# Sheet1.net
KiCad netlist of a schematic drawn in Altium Designer
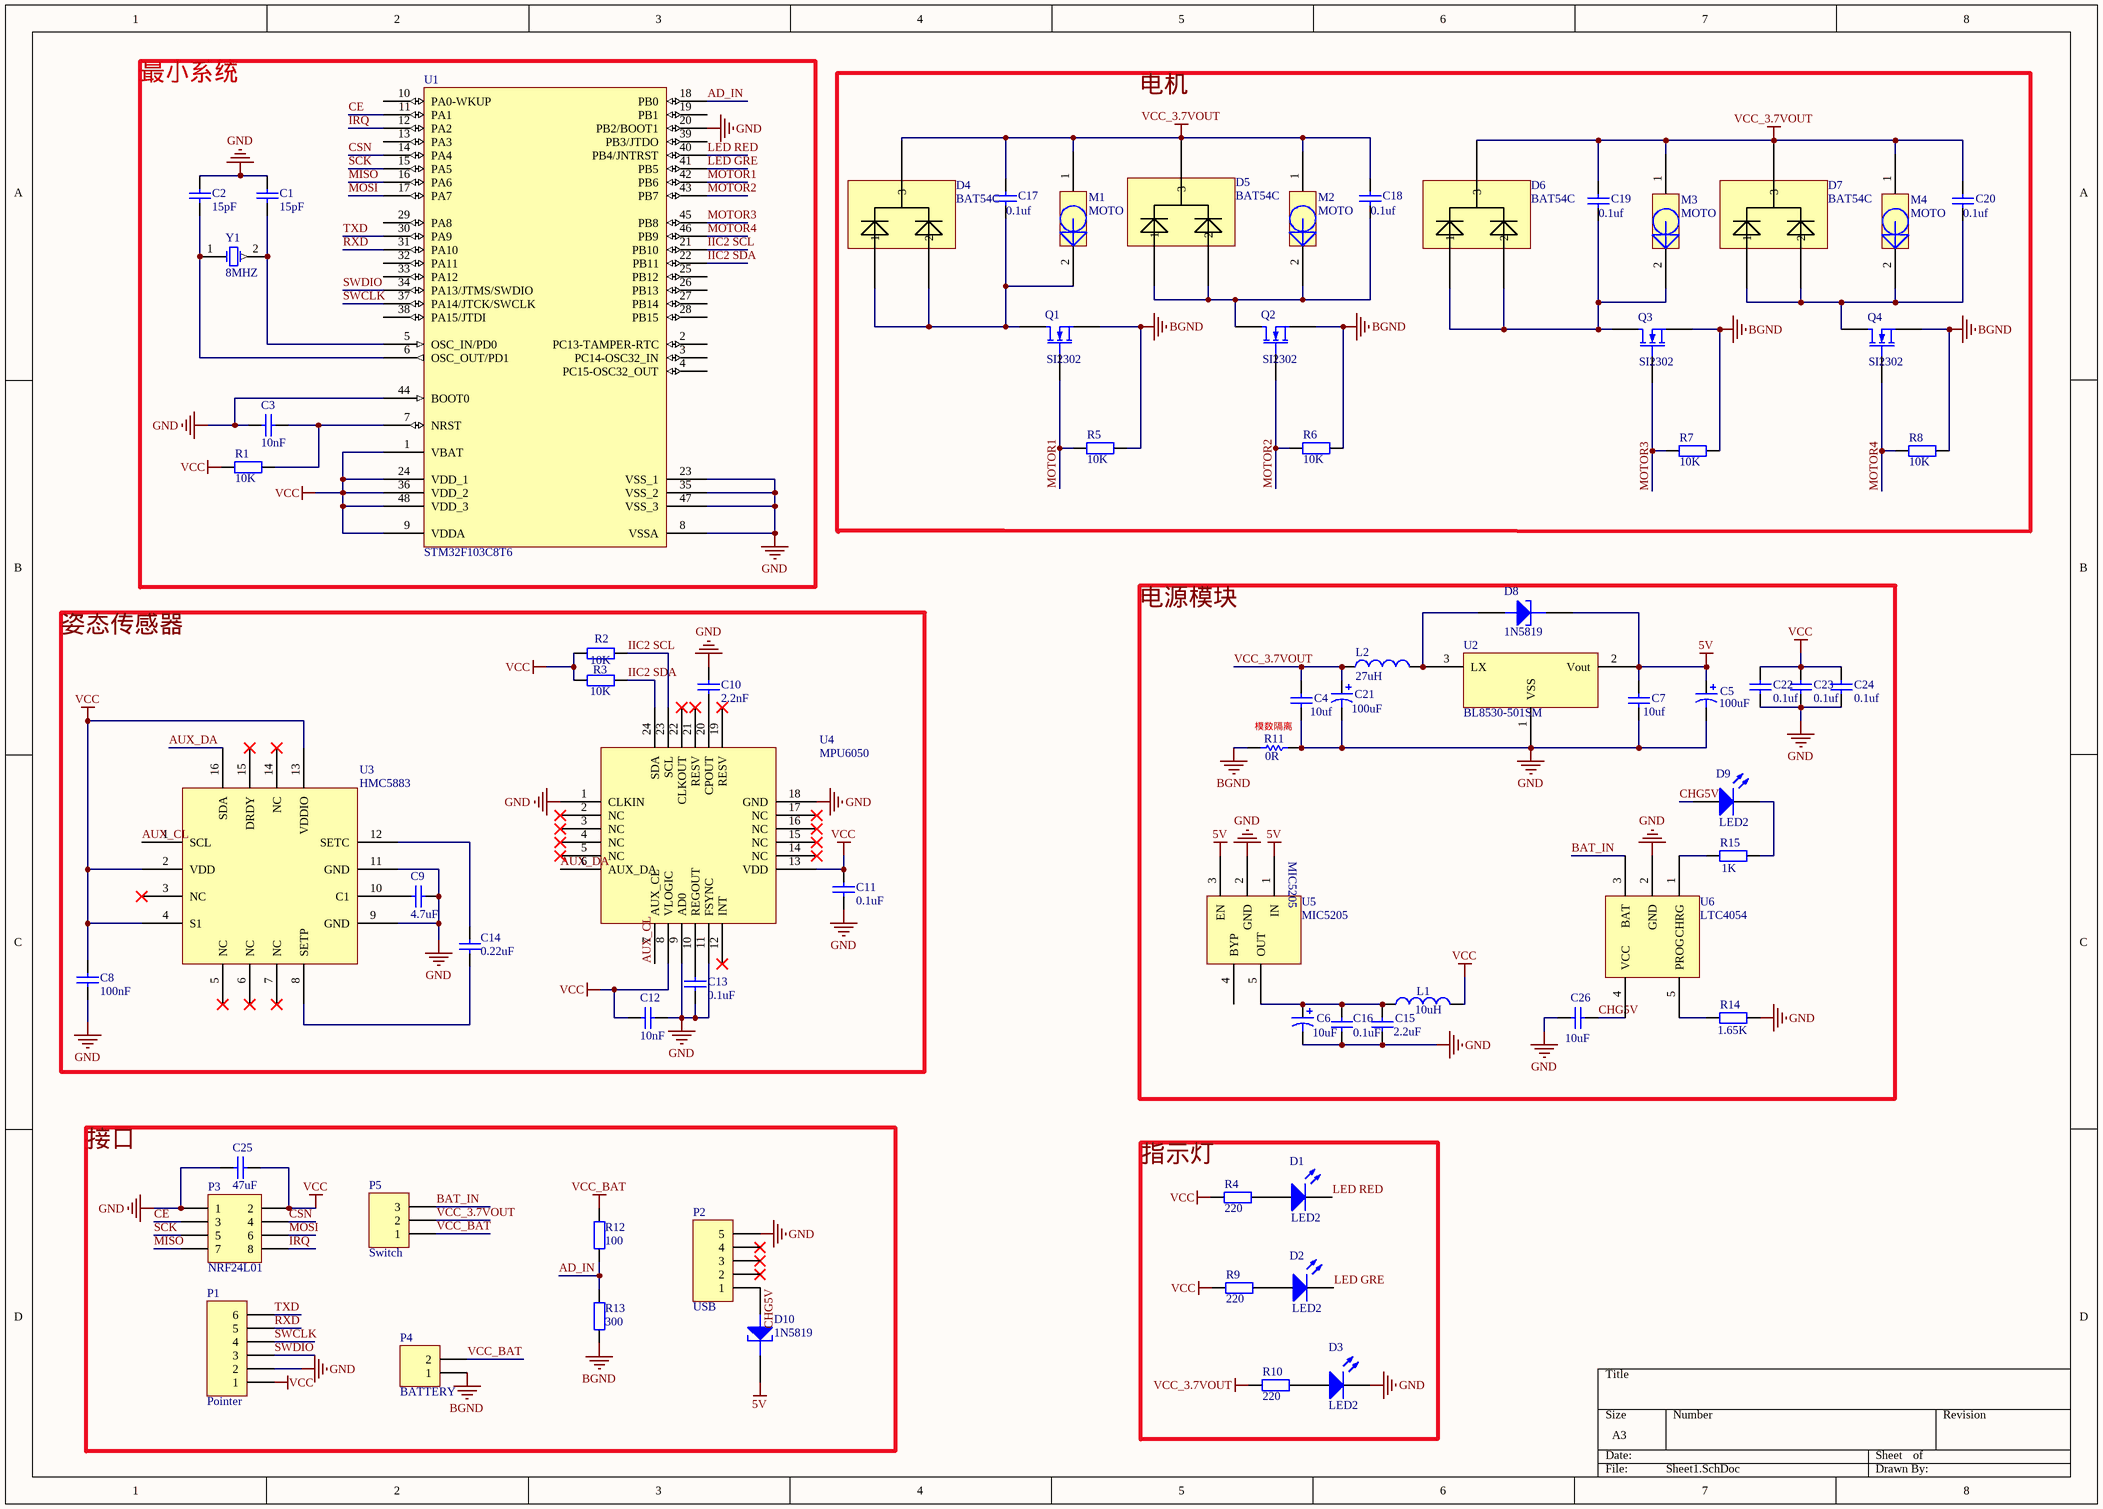
[diagram p0: Sheet1.SchDoc]

(export (version "E")
  (design (tool "Eeschema 10.0.6"))
  (components
    (comp (ref "C1")
      (value "15pF")
      (footprint "0603-N-CAP")
      (description "Capacitor (Semiconductor SIM Model)")
      (fields (field (name "Comment") "Cap Semi") (field (name "PUBLISHER") "Altium Limited"))
      (libsource (lib "Miscellaneous Devices") (part "Cap Semi"))
    )
    (comp (ref "C2")
      (value "15pF")
      (footprint "0603-N-CAP")
      (description "Capacitor (Semiconductor SIM Model)")
      (fields (field (name "Comment") "Cap Semi") (field (name "PUBLISHER") "Altium Limited"))
      (libsource (lib "Miscellaneous Devices") (part "Cap Semi"))
    )
    (comp (ref "C3")
      (value "10nF")
      (footprint "0603-N-CAP")
      (description "Capacitor (Semiconductor SIM Model)")
      (fields (field (name "Comment") "Cap Semi") (field (name "PUBLISHER") "Altium Limited"))
      (libsource (lib "Miscellaneous Devices") (part "Cap Semi"))
    )
    (comp (ref "C4")
      (value "10uf")
      (footprint "0603-N-CAP")
      (description "Capacitor")
      (fields (field (name "Comment") "Cap") (field (name "PUBLISHER") "Altium Limited"))
      (libsource (lib "Miscellaneous Devices") (part "Cap"))
    )
    (comp (ref "C5")
      (value "100uF")
      (footprint "1210")
      (description "Polarized Capacitor (Surface Mount)")
      (fields (field (name "Comment") "Cap Pol3") (field (name "PUBLISHER") "Altium Limited"))
      (libsource (lib "Miscellaneous Devices") (part "Cap Pol3"))
    )
    (comp (ref "C6")
      (value "10uF")
      (footprint "3216")
      (description "Polarized Capacitor (Surface Mount)")
      (fields (field (name "Comment") "Cap Pol3") (field (name "PUBLISHER") "Altium Limited"))
      (libsource (lib "Miscellaneous Devices") (part "Cap Pol3"))
    )
    (comp (ref "C7")
      (value "10uf")
      (footprint "0603-N-CAP")
      (description "Capacitor")
      (fields (field (name "Comment") "Cap") (field (name "PUBLISHER") "Altium Limited"))
      (libsource (lib "Miscellaneous Devices") (part "Cap"))
    )
    (comp (ref "C8")
      (value "100nF")
      (footprint "0603-N-CAP")
      (description "Capacitor (Semiconductor SIM Model)")
      (fields (field (name "Comment") "Cap Semi") (field (name "PUBLISHER") "Altium Limited"))
      (libsource (lib "Miscellaneous Devices") (part "Cap Semi"))
    )
    (comp (ref "C9")
      (value "4.7uF")
      (footprint "0603-N-CAP")
      (description "Capacitor (Semiconductor SIM Model)")
      (fields (field (name "Comment") "Cap Semi") (field (name "PUBLISHER") "Altium Limited"))
      (libsource (lib "Miscellaneous Devices") (part "Cap Semi"))
    )
    (comp (ref "C10")
      (value "2.2nF")
      (footprint "0603-N-CAP")
      (description "Capacitor (Semiconductor SIM Model)")
      (fields (field (name "Comment") "Cap Semi") (field (name "PUBLISHER") "Altium Limited"))
      (libsource (lib "Miscellaneous Devices") (part "Cap Semi"))
    )
    (comp (ref "C11")
      (value "0.1uF")
      (footprint "0603-N-CAP")
      (description "Capacitor (Semiconductor SIM Model)")
      (fields (field (name "Comment") "Cap Semi") (field (name "PUBLISHER") "Altium Limited"))
      (libsource (lib "Miscellaneous Devices") (part "Cap Semi"))
    )
    (comp (ref "C12")
      (value "10nF")
      (footprint "0603-N-CAP")
      (description "Capacitor (Semiconductor SIM Model)")
      (fields (field (name "Comment") "Cap Semi") (field (name "PUBLISHER") "Altium Limited"))
      (libsource (lib "Miscellaneous Devices") (part "Cap Semi"))
    )
    (comp (ref "C13")
      (value "0.1uF")
      (footprint "0603-N-CAP")
      (description "Capacitor (Semiconductor SIM Model)")
      (fields (field (name "Comment") "Cap Semi") (field (name "PUBLISHER") "Altium Limited"))
      (libsource (lib "Miscellaneous Devices") (part "Cap Semi"))
    )
    (comp (ref "C14")
      (value "0.22uF")
      (footprint "0603-N-CAP")
      (description "Capacitor (Semiconductor SIM Model)")
      (fields (field (name "Comment") "Cap Semi") (field (name "PUBLISHER") "Altium Limited"))
      (libsource (lib "Miscellaneous Devices") (part "Cap Semi"))
    )
    (comp (ref "C15")
      (value "2.2uF")
      (footprint "0603-N-CAP")
      (description "Capacitor")
      (fields (field (name "Comment") "Cap") (field (name "PUBLISHER") "Altium Limited"))
      (libsource (lib "Miscellaneous Devices") (part "Cap"))
    )
    (comp (ref "C16")
      (value "0.1uF")
      (footprint "0603-N-CAP")
      (description "Capacitor")
      (fields (field (name "Comment") "Cap") (field (name "PUBLISHER") "Altium Limited"))
      (libsource (lib "Miscellaneous Devices") (part "Cap"))
    )
    (comp (ref "C17")
      (value "0.1uf")
      (footprint "0603-N-CAP")
      (description "Capacitor")
      (fields (field (name "Comment") "Cap") (field (name "PUBLISHER") "Altium Limited"))
      (libsource (lib "Miscellaneous Devices") (part "Cap"))
    )
    (comp (ref "C18")
      (value "0.1uf")
      (footprint "0603-N-CAP")
      (description "Capacitor")
      (fields (field (name "Comment") "Cap") (field (name "PUBLISHER") "Altium Limited"))
      (libsource (lib "Miscellaneous Devices") (part "Cap"))
    )
    (comp (ref "C19")
      (value "0.1uf")
      (footprint "0603-N-CAP")
      (description "Capacitor")
      (fields (field (name "Comment") "Cap") (field (name "PUBLISHER") "Altium Limited"))
      (libsource (lib "Miscellaneous Devices") (part "Cap"))
    )
    (comp (ref "C20")
      (value "0.1uf")
      (footprint "0603-N-CAP")
      (description "Capacitor")
      (fields (field (name "Comment") "Cap") (field (name "PUBLISHER") "Altium Limited"))
      (libsource (lib "Miscellaneous Devices") (part "Cap"))
    )
    (comp (ref "C21")
      (value "100uF")
      (footprint "1210")
      (description "Polarized Capacitor (Surface Mount)")
      (fields (field (name "Comment") "Cap Pol3") (field (name "PUBLISHER") "Altium Limited"))
      (libsource (lib "Miscellaneous Devices") (part "Cap Pol3"))
    )
    (comp (ref "C22")
      (value "0.1uf")
      (footprint "0603-N-CAP")
      (description "Capacitor")
      (fields (field (name "Comment") "Cap") (field (name "PUBLISHER") "Altium Limited"))
      (libsource (lib "Miscellaneous Devices") (part "Cap"))
    )
    (comp (ref "C23")
      (value "0.1uf")
      (footprint "0603-N-CAP")
      (description "Capacitor")
      (fields (field (name "Comment") "Cap") (field (name "PUBLISHER") "Altium Limited"))
      (libsource (lib "Miscellaneous Devices") (part "Cap"))
    )
    (comp (ref "C24")
      (value "0.1uf")
      (footprint "0603-N-CAP")
      (description "Capacitor")
      (fields (field (name "Comment") "Cap") (field (name "PUBLISHER") "Altium Limited"))
      (libsource (lib "Miscellaneous Devices") (part "Cap"))
    )
    (comp (ref "C25")
      (value "47uF")
      (footprint "1206")
      (description "Capacitor (Semiconductor SIM Model)")
      (fields (field (name "Comment") "Cap Semi") (field (name "PUBLISHER") "Altium Limited"))
      (libsource (lib "Miscellaneous Devices") (part "Cap Semi"))
    )
    (comp (ref "C26")
      (value "10uF")
      (footprint "0603-N-CAP")
      (description "Capacitor")
      (fields (field (name "Comment") "Cap") (field (name "PUBLISHER") "Altium Limited"))
      (libsource (lib "Miscellaneous Devices") (part "Cap"))
    )
    (comp (ref "D1")
      (value "LED2")
      (footprint "6-0805_N")
      (description "Typical RED, GREEN, YELLOW, AMBER GaAs LED")
      (fields (field (name "PUBLISHER") "Altium Limited"))
      (libsource (lib "Miscellaneous Devices") (part "LED2"))
    )
    (comp (ref "D2")
      (value "LED2")
      (footprint "6-0805_N")
      (description "Typical RED, GREEN, YELLOW, AMBER GaAs LED")
      (fields (field (name "PUBLISHER") "Altium Limited"))
      (libsource (lib "Miscellaneous Devices") (part "LED2"))
    )
    (comp (ref "D3")
      (value "LED2")
      (footprint "6-0805_N")
      (description "Typical RED, GREEN, YELLOW, AMBER GaAs LED")
      (fields (field (name "PUBLISHER") "Altium Limited"))
      (libsource (lib "Miscellaneous Devices") (part "LED2"))
    )
    (comp (ref "D4") (value "BAT54C") (footprint "SOT-23") (libsource (lib "Mine") (part "BAT54C")))
    (comp (ref "D5") (value "BAT54C") (footprint "SOT-23") (libsource (lib "Mine") (part "BAT54C")))
    (comp (ref "D6") (value "BAT54C") (footprint "SOT-23") (libsource (lib "Mine") (part "BAT54C")))
    (comp (ref "D7") (value "BAT54C") (footprint "SOT-23") (libsource (lib "Mine") (part "BAT54C")))
    (comp (ref "D8")
      (value "1N5819")
      (footprint "1206")
      (description "Tunnel FDiode")
      (libsource (lib "二极管") (part "TUNNEL"))
    )
    (comp (ref "D9")
      (value "LED2")
      (footprint "6-0805_N")
      (description "Typical RED, GREEN, YELLOW, AMBER GaAs LED")
      (fields (field (name "PUBLISHER") "Altium Limited"))
      (libsource (lib "Miscellaneous Devices") (part "LED2"))
    )
    (comp (ref "D10")
      (value "1N5819")
      (footprint "1206")
      (description "Tunnel FDiode")
      (libsource (lib "二极管") (part "TUNNEL"))
    )
    (comp (ref "L1")
      (value "10uH")
      (footprint "0603-N-res")
      (description "Inductor")
      (fields (field (name "PUBLISHER") "Altium Limited"))
      (libsource (lib "Miscellaneous Devices") (part "Inductor"))
    )
    (comp (ref "L2")
      (value "27uH")
      (footprint "0603-N-res")
      (description "Inductor")
      (fields (field (name "PUBLISHER") "Altium Limited"))
      (libsource (lib "Miscellaneous Devices") (part "Inductor"))
    )
    (comp (ref "M1") (value "MOTO") (footprint "HDR1X2") (libsource (lib "Schlib1") (part "MOTO")))
    (comp (ref "M2") (value "MOTO") (footprint "HDR1X2") (libsource (lib "Schlib1") (part "MOTO")))
    (comp (ref "M3") (value "MOTO") (footprint "HDR1X2") (libsource (lib "Schlib1") (part "MOTO")))
    (comp (ref "M4") (value "MOTO") (footprint "HDR1X2") (libsource (lib "Schlib1") (part "MOTO")))
    (comp (ref "P1")
      (value "Pointer")
      (footprint "HDR1X6")
      (description "Header, 6-Pin")
      (fields (field (name "PUBLISHER") "Altium Limited"))
      (libsource (lib "Miscellaneous Connectors") (part "Header 6"))
    )
    (comp (ref "P2")
      (value "USB")
      (footprint "Micro Usb")
      (description "Header, 5-Pin")
      (fields (field (name "PUBLISHER") "Altium Limited"))
      (libsource (lib "Miscellaneous Connectors") (part "Header 5"))
    )
    (comp (ref "P3")
      (value "NRF24L01")
      (footprint "head 4X2")
      (description "Header, 4-Pin, Dual row, Right Angle")
      (fields (field (name "PUBLISHER") "Altium Limited"))
      (libsource (lib "Miscellaneous Connectors") (part "Header 4X2H"))
    )
    (comp (ref "P4")
      (value "BATTERY")
      (footprint "HDR1X2")
      (description "Header, 2-Pin")
      (fields (field (name "PUBLISHER") "Altium Limited"))
      (libsource (lib "Miscellaneous Connectors") (part "Header 2"))
    )
    (comp (ref "P5")
      (value "Switch")
      (footprint "HDR1X3")
      (description "Header, 3-Pin")
      (fields (field (name "PUBLISHER") "Altium Limited"))
      (libsource (lib "Miscellaneous Connectors") (part "Header 3"))
    )
    (comp (ref "Q1")
      (value "SI2302")
      (footprint "SOT-23")
      (description "N-Channel MOSFET")
      (fields (field (name "PUBLISHER") "Altium Limited"))
      (libsource (lib "Miscellaneous Devices") (part "MOSFET-N"))
    )
    (comp (ref "Q2")
      (value "SI2302")
      (footprint "SOT-23")
      (description "N-Channel MOSFET")
      (fields (field (name "PUBLISHER") "Altium Limited"))
      (libsource (lib "Miscellaneous Devices") (part "MOSFET-N"))
    )
    (comp (ref "Q3")
      (value "SI2302")
      (footprint "SOT-23")
      (description "N-Channel MOSFET")
      (fields (field (name "PUBLISHER") "Altium Limited"))
      (libsource (lib "Miscellaneous Devices") (part "MOSFET-N"))
    )
    (comp (ref "Q4")
      (value "SI2302")
      (footprint "SOT-23")
      (description "N-Channel MOSFET")
      (fields (field (name "PUBLISHER") "Altium Limited"))
      (libsource (lib "Miscellaneous Devices") (part "MOSFET-N"))
    )
    (comp (ref "R1")
      (value "10K")
      (footprint "0603-N-res")
      (description "Resistor")
      (fields (field (name "Comment") "Res2") (field (name "PUBLISHER") "Altium Limited"))
      (libsource (lib "Miscellaneous Devices") (part "Res2"))
    )
    (comp (ref "R2")
      (value "10K")
      (footprint "0603-N-res")
      (description "Resistor")
      (fields (field (name "Comment") "Res2") (field (name "PUBLISHER") "Altium Limited"))
      (libsource (lib "Miscellaneous Devices") (part "Res2"))
    )
    (comp (ref "R3")
      (value "10K")
      (footprint "0603-N-res")
      (description "Resistor")
      (fields (field (name "Comment") "Res2") (field (name "PUBLISHER") "Altium Limited"))
      (libsource (lib "Miscellaneous Devices") (part "Res2"))
    )
    (comp (ref "R4")
      (value "220")
      (footprint "0603-N-res")
      (description "Resistor")
      (fields (field (name "Comment") "Res2") (field (name "PUBLISHER") "Altium Limited"))
      (libsource (lib "Miscellaneous Devices") (part "Res2"))
    )
    (comp (ref "R5")
      (value "10K")
      (footprint "0603-N-res")
      (description "Resistor")
      (fields (field (name "Comment") "Res2") (field (name "PUBLISHER") "Altium Limited"))
      (libsource (lib "Miscellaneous Devices") (part "Res2"))
    )
    (comp (ref "R6")
      (value "10K")
      (footprint "0603-N-res")
      (description "Resistor")
      (fields (field (name "Comment") "Res2") (field (name "PUBLISHER") "Altium Limited"))
      (libsource (lib "Miscellaneous Devices") (part "Res2"))
    )
    (comp (ref "R7")
      (value "10K")
      (footprint "0603-N-res")
      (description "Resistor")
      (fields (field (name "Comment") "Res2") (field (name "PUBLISHER") "Altium Limited"))
      (libsource (lib "Miscellaneous Devices") (part "Res2"))
    )
    (comp (ref "R8")
      (value "10K")
      (footprint "0603-N-res")
      (description "Resistor")
      (fields (field (name "Comment") "Res2") (field (name "PUBLISHER") "Altium Limited"))
      (libsource (lib "Miscellaneous Devices") (part "Res2"))
    )
    (comp (ref "R9")
      (value "220")
      (footprint "0603-N-res")
      (description "Resistor")
      (fields (field (name "Comment") "Res2") (field (name "PUBLISHER") "Altium Limited"))
      (libsource (lib "Miscellaneous Devices") (part "Res2"))
    )
    (comp (ref "R10")
      (value "220")
      (footprint "0603-N-res")
      (description "Resistor")
      (fields (field (name "Comment") "Res2") (field (name "PUBLISHER") "Altium Limited"))
      (libsource (lib "Miscellaneous Devices") (part "Res2"))
    )
    (comp (ref "R11")
      (value "0R")
      (footprint "0603-N-res")
      (description "Resistor")
      (fields (field (name "Comment") "Res1") (field (name "PUBLISHER") "Altium Limited"))
      (libsource (lib "Miscellaneous Devices") (part "Res1"))
    )
    (comp (ref "R12")
      (value "100")
      (footprint "0603-N-res")
      (description "Resistor")
      (fields (field (name "Comment") "Res2") (field (name "PUBLISHER") "Altium Limited"))
      (libsource (lib "") (part "Res2_1"))
    )
    (comp (ref "R13")
      (value "300")
      (footprint "0603-N-res")
      (description "Resistor")
      (fields (field (name "Comment") "Res2") (field (name "PUBLISHER") "Altium Limited"))
      (libsource (lib "") (part "Res2_1"))
    )
    (comp (ref "R14")
      (value "1.65K")
      (footprint "0603-N-res")
      (description "Resistor")
      (fields (field (name "Comment") "Res2") (field (name "PUBLISHER") "Altium Limited"))
      (libsource (lib "") (part "Res2_2"))
    )
    (comp (ref "R15")
      (value "1K")
      (footprint "0603-N-res")
      (description "Resistor")
      (fields (field (name "Comment") "Res2") (field (name "PUBLISHER") "Altium Limited"))
      (libsource (lib "") (part "Res2_2"))
    )
    (comp (ref "U1")
      (value "STM32F103C8T6")
      (footprint "LQFP48_N")
      (description "STM32 ARM-based 32-bit MCU with 64 Kbytes Flash, 48-pin LQFP, Industrial Temperature")
      (fields (field (name "PUBLISHER") "Altium Limited"))
      (libsource (lib "ST Microcontroller 32-Bit STM32") (part "STM32F103C8T6"))
    )
    (comp (ref "U2")
      (value "BL8530-501SM")
      (footprint "SOT223")
      (libsource (lib "Schlib1") (part "ME620633"))
    )
    (comp (ref "U3") (value "HMC5883") (footprint "HMC5883L") (libsource (lib "Mine") (part "HMC5883")))
    (comp (ref "U4") (value "MPU6050") (footprint "MPU 6050") (libsource (lib "Mine") (part "MPU6050")))
    (comp (ref "U5")
      (value "MIC5205")
      (footprint "MIC5205")
      (description "5V降压到3.3V")
      (libsource (lib "Schlib1") (part "MIC5205"))
    )
    (comp (ref "U6") (value "LTC4054") (footprint "MIC5205") (libsource (lib "Mine") (part "LTC4054")))
    (comp (ref "Y1")
      (value "8MHZ")
      (footprint "XTAL1")
      (description "Crystal Oscillator")
      (fields (field (name "PUBLISHER") "Altium Limited"))
      (libsource (lib "Miscellaneous Devices") (part "XTAL"))
    )
  )
  (nets
    (net (code "1") (name "/AD_IN") (class "Default")
      (node (ref "R12") (pin "1") (pinfunction "1_1") (pintype "passive"))
      (node (ref "R13") (pin "2") (pinfunction "2_2") (pintype "passive"))
      (node (ref "U1") (pin "18") (pinfunction "PB0_18") (pintype "bidirectional"))
    )
    (net (code "2") (name "/AUX_CL") (class "Default")
      (node (ref "U3") (pin "1") (pinfunction "SCL_1") (pintype "passive"))
      (node (ref "U4") (pin "7") (pinfunction "AUX_CL_7") (pintype "passive"))
    )
    (net (code "3") (name "/AUX_DA") (class "Default")
      (node (ref "U3") (pin "16") (pinfunction "SDA_16") (pintype "passive"))
      (node (ref "U4") (pin "6") (pinfunction "AUX_DA_6") (pintype "passive"))
    )
    (net (code "4") (name "/BAT_IN") (class "Default")
      (node (ref "P5") (pin "3") (pinfunction "3_3") (pintype "passive"))
      (node (ref "U6") (pin "3") (pinfunction "BAT_3") (pintype "passive"))
    )
    (net (code "5") (name "/CE") (class "Default")
      (node (ref "P3") (pin "3") (pinfunction "3_3") (pintype "passive"))
      (node (ref "U1") (pin "11") (pinfunction "PA1_11") (pintype "bidirectional"))
    )
    (net (code "6") (name "/CHG5V") (class "Default")
      (node (ref "C26") (pin "2") (pinfunction "2_2") (pintype "passive"))
      (node (ref "D10") (pin "1") (pinfunction "A_1") (pintype "passive"))
      (node (ref "D9") (pin "1") (pinfunction "A_1") (pintype "passive"))
      (node (ref "P2") (pin "1") (pinfunction "1_1") (pintype "passive"))
      (node (ref "U6") (pin "4") (pinfunction "VCC_4") (pintype "passive"))
    )
    (net (code "7") (name "/CSN") (class "Default")
      (node (ref "P3") (pin "4") (pinfunction "4_4") (pintype "passive"))
      (node (ref "U1") (pin "14") (pinfunction "PA4_14") (pintype "bidirectional"))
    )
    (net (code "8") (name "/IIC2 SCL") (class "Default")
      (node (ref "R2") (pin "1") (pinfunction "1_1") (pintype "passive"))
      (node (ref "U1") (pin "21") (pinfunction "PB10_21") (pintype "bidirectional"))
      (node (ref "U4") (pin "23") (pinfunction "SCL_23") (pintype "passive"))
    )
    (net (code "9") (name "/IIC2 SDA") (class "Default")
      (node (ref "R3") (pin "1") (pinfunction "1_1") (pintype "passive"))
      (node (ref "U1") (pin "22") (pinfunction "PB11_22") (pintype "bidirectional"))
      (node (ref "U4") (pin "24") (pinfunction "SDA_24") (pintype "passive"))
    )
    (net (code "10") (name "/IRQ") (class "Default")
      (node (ref "P3") (pin "8") (pinfunction "8_8") (pintype "passive"))
      (node (ref "U1") (pin "12") (pinfunction "PA2_12") (pintype "bidirectional"))
    )
    (net (code "11") (name "/LED GRE") (class "Default")
      (node (ref "D2") (pin "2") (pinfunction "K_2") (pintype "passive"))
      (node (ref "U1") (pin "41") (pinfunction "PB5_41") (pintype "bidirectional"))
    )
    (net (code "12") (name "/LED RED") (class "Default")
      (node (ref "D1") (pin "2") (pinfunction "K_2") (pintype "passive"))
      (node (ref "U1") (pin "40") (pinfunction "PB4/JNTRST_40") (pintype "bidirectional"))
    )
    (net (code "13") (name "/MISO") (class "Default")
      (node (ref "P3") (pin "7") (pinfunction "7_7") (pintype "passive"))
      (node (ref "U1") (pin "16") (pinfunction "PA6_16") (pintype "bidirectional"))
    )
    (net (code "14") (name "/MOSI") (class "Default")
      (node (ref "P3") (pin "6") (pinfunction "6_6") (pintype "passive"))
      (node (ref "U1") (pin "17") (pinfunction "PA7_17") (pintype "bidirectional"))
    )
    (net (code "15") (name "/MOTOR1") (class "Default")
      (node (ref "Q1") (pin "2") (pinfunction "G_2") (pintype "passive"))
      (node (ref "R5") (pin "2") (pinfunction "2_2") (pintype "passive"))
      (node (ref "U1") (pin "42") (pinfunction "PB6_42") (pintype "bidirectional"))
    )
    (net (code "16") (name "/MOTOR2") (class "Default")
      (node (ref "Q2") (pin "2") (pinfunction "G_2") (pintype "passive"))
      (node (ref "R6") (pin "2") (pinfunction "2_2") (pintype "passive"))
      (node (ref "U1") (pin "43") (pinfunction "PB7_43") (pintype "bidirectional"))
    )
    (net (code "17") (name "/MOTOR3") (class "Default")
      (node (ref "Q3") (pin "2") (pinfunction "G_2") (pintype "passive"))
      (node (ref "R7") (pin "2") (pinfunction "2_2") (pintype "passive"))
      (node (ref "U1") (pin "45") (pinfunction "PB8_45") (pintype "bidirectional"))
    )
    (net (code "18") (name "/MOTOR4") (class "Default")
      (node (ref "Q4") (pin "2") (pinfunction "G_2") (pintype "passive"))
      (node (ref "R8") (pin "2") (pinfunction "2_2") (pintype "passive"))
      (node (ref "U1") (pin "46") (pinfunction "PB9_46") (pintype "bidirectional"))
    )
    (net (code "19") (name "/RXD") (class "Default")
      (node (ref "P1") (pin "5") (pinfunction "5_5") (pintype "passive"))
      (node (ref "U1") (pin "31") (pinfunction "PA10_31") (pintype "bidirectional"))
    )
    (net (code "20") (name "/SCK") (class "Default")
      (node (ref "P3") (pin "5") (pinfunction "5_5") (pintype "passive"))
      (node (ref "U1") (pin "15") (pinfunction "PA5_15") (pintype "bidirectional"))
    )
    (net (code "21") (name "/SWCLK") (class "Default")
      (node (ref "P1") (pin "4") (pinfunction "4_4") (pintype "passive"))
      (node (ref "U1") (pin "37") (pinfunction "PA14/JTCK/SWCLK_37") (pintype "bidirectional"))
    )
    (net (code "22") (name "/SWDIO") (class "Default")
      (node (ref "P1") (pin "3") (pinfunction "3_3") (pintype "passive"))
      (node (ref "U1") (pin "34") (pinfunction "PA13/JTMS/SWDIO_34") (pintype "bidirectional"))
    )
    (net (code "23") (name "/TXD") (class "Default")
      (node (ref "P1") (pin "6") (pinfunction "6_6") (pintype "passive"))
      (node (ref "U1") (pin "30") (pinfunction "PA9_30") (pintype "bidirectional"))
    )
    (net (code "24") (name "5V") (class "Default")
      (node (ref "C5") (pin "1") (pinfunction "1_1") (pintype "passive"))
      (node (ref "C7") (pin "2") (pinfunction "2_2") (pintype "passive"))
      (node (ref "D10") (pin "2") (pinfunction "K_2") (pintype "passive"))
      (node (ref "D8") (pin "2") (pinfunction "K_2") (pintype "passive"))
      (node (ref "U2") (pin "2") (pinfunction "Vout_2") (pintype "passive"))
      (node (ref "U5") (pin "1") (pinfunction "IN_1") (pintype "passive"))
      (node (ref "U5") (pin "3") (pinfunction "EN_3") (pintype "passive"))
    )
    (net (code "25") (name "BGND") (class "Default")
      (node (ref "P4") (pin "1") (pinfunction "1_1") (pintype "passive"))
      (node (ref "Q1") (pin "3") (pinfunction "S_3") (pintype "passive"))
      (node (ref "Q2") (pin "3") (pinfunction "S_3") (pintype "passive"))
      (node (ref "Q3") (pin "3") (pinfunction "S_3") (pintype "passive"))
      (node (ref "Q4") (pin "3") (pinfunction "S_3") (pintype "passive"))
      (node (ref "R11") (pin "1") (pinfunction "1_1") (pintype "passive"))
      (node (ref "R13") (pin "1") (pinfunction "1_1") (pintype "passive"))
      (node (ref "R5") (pin "1") (pinfunction "1_1") (pintype "passive"))
      (node (ref "R6") (pin "1") (pinfunction "1_1") (pintype "passive"))
      (node (ref "R7") (pin "1") (pinfunction "1_1") (pintype "passive"))
      (node (ref "R8") (pin "1") (pinfunction "1_1") (pintype "passive"))
    )
    (net (code "26") (name "GND") (class "Default")
      (node (ref "C1") (pin "1") (pinfunction "1_1") (pintype "passive"))
      (node (ref "C10") (pin "2") (pinfunction "2_2") (pintype "passive"))
      (node (ref "C11") (pin "1") (pinfunction "1_1") (pintype "passive"))
      (node (ref "C12") (pin "2") (pinfunction "2_2") (pintype "passive"))
      (node (ref "C13") (pin "1") (pinfunction "1_1") (pintype "passive"))
      (node (ref "C15") (pin "1") (pinfunction "1_1") (pintype "passive"))
      (node (ref "C16") (pin "1") (pinfunction "1_1") (pintype "passive"))
      (node (ref "C2") (pin "2") (pinfunction "2_2") (pintype "passive"))
      (node (ref "C21") (pin "2") (pinfunction "2_2") (pintype "passive"))
      (node (ref "C22") (pin "1") (pinfunction "1_1") (pintype "passive"))
      (node (ref "C23") (pin "1") (pinfunction "1_1") (pintype "passive"))
      (node (ref "C24") (pin "1") (pinfunction "1_1") (pintype "passive"))
      (node (ref "C25") (pin "1") (pinfunction "1_1") (pintype "passive"))
      (node (ref "C26") (pin "1") (pinfunction "1_1") (pintype "passive"))
      (node (ref "C3") (pin "1") (pinfunction "1_1") (pintype "passive"))
      (node (ref "C4") (pin "1") (pinfunction "1_1") (pintype "passive"))
      (node (ref "C5") (pin "2") (pinfunction "2_2") (pintype "passive"))
      (node (ref "C6") (pin "2") (pinfunction "2_2") (pintype "passive"))
      (node (ref "C7") (pin "1") (pinfunction "1_1") (pintype "passive"))
      (node (ref "C8") (pin "1") (pinfunction "1_1") (pintype "passive"))
      (node (ref "C9") (pin "1") (pinfunction "1_1") (pintype "passive"))
      (node (ref "D3") (pin "2") (pinfunction "K_2") (pintype "passive"))
      (node (ref "P1") (pin "2") (pinfunction "2_2") (pintype "passive"))
      (node (ref "P2") (pin "5") (pinfunction "5_5") (pintype "passive"))
      (node (ref "P3") (pin "1") (pinfunction "1_1") (pintype "passive"))
      (node (ref "R11") (pin "2") (pinfunction "2_2") (pintype "passive"))
      (node (ref "R14") (pin "2") (pinfunction "2_2") (pintype "passive"))
      (node (ref "U1") (pin "20") (pinfunction "PB2/BOOT1_20") (pintype "bidirectional"))
      (node (ref "U1") (pin "23") (pinfunction "VSS_1_23") (pintype "power_in"))
      (node (ref "U1") (pin "35") (pinfunction "VSS_2_35") (pintype "power_in"))
      (node (ref "U1") (pin "44") (pinfunction "BOOT0_44") (pintype "input"))
      (node (ref "U1") (pin "47") (pinfunction "VSS_3_47") (pintype "power_in"))
      (node (ref "U1") (pin "8") (pinfunction "VSSA_8") (pintype "power_in"))
      (node (ref "U2") (pin "1") (pinfunction "VSS_1") (pintype "passive"))
      (node (ref "U3") (pin "11") (pinfunction "GND_11") (pintype "passive"))
      (node (ref "U3") (pin "9") (pinfunction "GND_9") (pintype "passive"))
      (node (ref "U4") (pin "1") (pinfunction "CLKIN_1") (pintype "passive"))
      (node (ref "U4") (pin "11") (pinfunction "FSYNC_11") (pintype "passive"))
      (node (ref "U4") (pin "18") (pinfunction "GND_18") (pintype "passive"))
      (node (ref "U4") (pin "9") (pinfunction "AD0_9") (pintype "passive"))
      (node (ref "U5") (pin "2") (pinfunction "GND_2") (pintype "passive"))
      (node (ref "U6") (pin "2") (pinfunction "GND_2") (pintype "passive"))
    )
    (net (code "27") (name "Net-(D1-A)") (class "Default")
      (node (ref "D1") (pin "1") (pinfunction "A_1") (pintype "passive"))
      (node (ref "R4") (pin "1") (pinfunction "1_1") (pintype "passive"))
    )
    (net (code "28") (name "Net-(D2-A)") (class "Default")
      (node (ref "D2") (pin "1") (pinfunction "A_1") (pintype "passive"))
      (node (ref "R9") (pin "1") (pinfunction "1_1") (pintype "passive"))
    )
    (net (code "29") (name "Net-(D3-A)") (class "Default")
      (node (ref "D3") (pin "1") (pinfunction "A_1") (pintype "passive"))
      (node (ref "R10") (pin "1") (pinfunction "1_1") (pintype "passive"))
    )
    (net (code "30") (name "Net-(D8-A)") (class "Default")
      (node (ref "D8") (pin "1") (pinfunction "A_1") (pintype "passive"))
      (node (ref "L2") (pin "2") (pinfunction "2_2") (pintype "passive"))
      (node (ref "U2") (pin "3") (pinfunction "LX_3") (pintype "passive"))
    )
    (net (code "31") (name "Net-(D9-K)") (class "Default")
      (node (ref "D9") (pin "2") (pinfunction "K_2") (pintype "passive"))
      (node (ref "R15") (pin "2") (pinfunction "2_2") (pintype "passive"))
    )
    (net (code "32") (name "Net-(Q1-D)") (class "Default")
      (node (ref "C17") (pin "1") (pinfunction "1_1") (pintype "passive"))
      (node (ref "D4") (pin "1") (pinfunction "1_1") (pintype "passive"))
      (node (ref "D4") (pin "2") (pinfunction "2_2") (pintype "passive"))
      (node (ref "M1") (pin "2") (pintype "passive"))
      (node (ref "Q1") (pin "1") (pinfunction "D_1") (pintype "passive"))
    )
    (net (code "33") (name "Net-(Q2-D)") (class "Default")
      (node (ref "C18") (pin "1") (pinfunction "1_1") (pintype "passive"))
      (node (ref "D5") (pin "1") (pinfunction "1_1") (pintype "passive"))
      (node (ref "D5") (pin "2") (pinfunction "2_2") (pintype "passive"))
      (node (ref "M2") (pin "2") (pintype "passive"))
      (node (ref "Q2") (pin "1") (pinfunction "D_1") (pintype "passive"))
    )
    (net (code "34") (name "Net-(Q3-D)") (class "Default")
      (node (ref "C19") (pin "1") (pinfunction "1_1") (pintype "passive"))
      (node (ref "D6") (pin "1") (pinfunction "1_1") (pintype "passive"))
      (node (ref "D6") (pin "2") (pinfunction "2_2") (pintype "passive"))
      (node (ref "M3") (pin "2") (pintype "passive"))
      (node (ref "Q3") (pin "1") (pinfunction "D_1") (pintype "passive"))
    )
    (net (code "35") (name "Net-(Q4-D)") (class "Default")
      (node (ref "C20") (pin "1") (pinfunction "1_1") (pintype "passive"))
      (node (ref "D7") (pin "1") (pinfunction "1_1") (pintype "passive"))
      (node (ref "D7") (pin "2") (pinfunction "2_2") (pintype "passive"))
      (node (ref "M4") (pin "2") (pintype "passive"))
      (node (ref "Q4") (pin "1") (pinfunction "D_1") (pintype "passive"))
    )
    (net (code "36") (name "Net-(U1-NRST)") (class "Default")
      (node (ref "C3") (pin "2") (pinfunction "2_2") (pintype "passive"))
      (node (ref "R1") (pin "1") (pinfunction "1_1") (pintype "passive"))
      (node (ref "U1") (pin "7") (pinfunction "NRST_7") (pintype "bidirectional"))
    )
    (net (code "37") (name "Net-(U1-OSC_IN{slash}PD0)") (class "Default")
      (node (ref "C1") (pin "2") (pinfunction "2_2") (pintype "passive"))
      (node (ref "U1") (pin "5") (pinfunction "OSC_IN/PD0_5") (pintype "input"))
      (node (ref "Y1") (pin "2") (pinfunction "OSC2_2") (pintype "output"))
    )
    (net (code "38") (name "Net-(U1-OSC_OUT{slash}PD1)") (class "Default")
      (node (ref "C2") (pin "1") (pinfunction "1_1") (pintype "passive"))
      (node (ref "U1") (pin "6") (pinfunction "OSC_OUT/PD1_6") (pintype "output"))
      (node (ref "Y1") (pin "1") (pinfunction "OSC1_1") (pintype "passive"))
    )
    (net (code "39") (name "Net-(U3-C1)") (class "Default")
      (node (ref "C9") (pin "2") (pinfunction "2_2") (pintype "passive"))
      (node (ref "U3") (pin "10") (pinfunction "C1_10") (pintype "passive"))
    )
    (net (code "40") (name "Net-(U3-SETC)") (class "Default")
      (node (ref "C14") (pin "1") (pinfunction "1_1") (pintype "passive"))
      (node (ref "U3") (pin "12") (pinfunction "SETC_12") (pintype "passive"))
    )
    (net (code "41") (name "Net-(U3-SETP)") (class "Default")
      (node (ref "C14") (pin "2") (pinfunction "2_2") (pintype "passive"))
      (node (ref "U3") (pin "8") (pinfunction "SETP_8") (pintype "passive"))
    )
    (net (code "42") (name "Net-(U4-CPOUT)") (class "Default")
      (node (ref "C10") (pin "1") (pinfunction "1_1") (pintype "passive"))
      (node (ref "U4") (pin "20") (pinfunction "CPOUT_20") (pintype "passive"))
    )
    (net (code "43") (name "Net-(U4-REGOUT)") (class "Default")
      (node (ref "C13") (pin "2") (pinfunction "2_2") (pintype "passive"))
      (node (ref "U4") (pin "10") (pinfunction "REGOUT_10") (pintype "passive"))
    )
    (net (code "44") (name "Net-(U5-OUT)") (class "Default")
      (node (ref "C15") (pin "2") (pinfunction "2_2") (pintype "passive"))
      (node (ref "C16") (pin "2") (pinfunction "2_2") (pintype "passive"))
      (node (ref "C6") (pin "1") (pinfunction "1_1") (pintype "passive"))
      (node (ref "L1") (pin "1") (pinfunction "1_1") (pintype "passive"))
      (node (ref "U5") (pin "5") (pinfunction "OUT_5") (pintype "passive"))
    )
    (net (code "45") (name "Net-(U6-CHRG)") (class "Default")
      (node (ref "R15") (pin "1") (pinfunction "1_1") (pintype "passive"))
      (node (ref "U6") (pin "1") (pinfunction "CHRG_1") (pintype "passive"))
    )
    (net (code "46") (name "Net-(U6-PROG)") (class "Default")
      (node (ref "R14") (pin "1") (pinfunction "1_1") (pintype "passive"))
      (node (ref "U6") (pin "5") (pinfunction "PROG_5") (pintype "passive"))
    )
    (net (code "47") (name "VCC") (class "Default")
      (node (ref "C11") (pin "2") (pinfunction "2_2") (pintype "passive"))
      (node (ref "C12") (pin "1") (pinfunction "1_1") (pintype "passive"))
      (node (ref "C22") (pin "2") (pinfunction "2_2") (pintype "passive"))
      (node (ref "C23") (pin "2") (pinfunction "2_2") (pintype "passive"))
      (node (ref "C24") (pin "2") (pinfunction "2_2") (pintype "passive"))
      (node (ref "C25") (pin "2") (pinfunction "2_2") (pintype "passive"))
      (node (ref "C8") (pin "2") (pinfunction "2_2") (pintype "passive"))
      (node (ref "L1") (pin "2") (pinfunction "2_2") (pintype "passive"))
      (node (ref "P1") (pin "1") (pinfunction "1_1") (pintype "passive"))
      (node (ref "P3") (pin "2") (pinfunction "2_2") (pintype "passive"))
      (node (ref "R1") (pin "2") (pinfunction "2_2") (pintype "passive"))
      (node (ref "R2") (pin "2") (pinfunction "2_2") (pintype "passive"))
      (node (ref "R3") (pin "2") (pinfunction "2_2") (pintype "passive"))
      (node (ref "R4") (pin "2") (pinfunction "2_2") (pintype "passive"))
      (node (ref "R9") (pin "2") (pinfunction "2_2") (pintype "passive"))
      (node (ref "U1") (pin "1") (pinfunction "VBAT_1") (pintype "power_in"))
      (node (ref "U1") (pin "24") (pinfunction "VDD_1_24") (pintype "power_in"))
      (node (ref "U1") (pin "36") (pinfunction "VDD_2_36") (pintype "power_in"))
      (node (ref "U1") (pin "48") (pinfunction "VDD_3_48") (pintype "power_in"))
      (node (ref "U1") (pin "9") (pinfunction "VDDA_9") (pintype "power_in"))
      (node (ref "U3") (pin "13") (pinfunction "VDDIO_13") (pintype "passive"))
      (node (ref "U3") (pin "2") (pinfunction "VDD_2") (pintype "passive"))
      (node (ref "U3") (pin "4") (pinfunction "S1_4") (pintype "passive"))
      (node (ref "U4") (pin "13") (pinfunction "VDD_13") (pintype "passive"))
      (node (ref "U4") (pin "8") (pinfunction "VLOGIC_8") (pintype "passive"))
    )
    (net (code "48") (name "VCC_3.7VOUT") (class "Default")
      (node (ref "C17") (pin "2") (pinfunction "2_2") (pintype "passive"))
      (node (ref "C18") (pin "2") (pinfunction "2_2") (pintype "passive"))
      (node (ref "C19") (pin "2") (pinfunction "2_2") (pintype "passive"))
      (node (ref "C20") (pin "2") (pinfunction "2_2") (pintype "passive"))
      (node (ref "C21") (pin "1") (pinfunction "1_1") (pintype "passive"))
      (node (ref "C4") (pin "2") (pinfunction "2_2") (pintype "passive"))
      (node (ref "D4") (pin "3") (pinfunction "3_3") (pintype "passive"))
      (node (ref "D5") (pin "3") (pinfunction "3_3") (pintype "passive"))
      (node (ref "D6") (pin "3") (pinfunction "3_3") (pintype "passive"))
      (node (ref "D7") (pin "3") (pinfunction "3_3") (pintype "passive"))
      (node (ref "L2") (pin "1") (pinfunction "1_1") (pintype "passive"))
      (node (ref "M1") (pin "1") (pintype "passive"))
      (node (ref "M2") (pin "1") (pintype "passive"))
      (node (ref "M3") (pin "1") (pintype "passive"))
      (node (ref "M4") (pin "1") (pintype "passive"))
      (node (ref "P5") (pin "2") (pinfunction "2_2") (pintype "passive"))
      (node (ref "R10") (pin "2") (pinfunction "2_2") (pintype "passive"))
    )
    (net (code "49") (name "VCC_BAT") (class "Default")
      (node (ref "P4") (pin "2") (pinfunction "2_2") (pintype "passive"))
      (node (ref "P5") (pin "1") (pinfunction "1_1") (pintype "passive"))
      (node (ref "R12") (pin "2") (pinfunction "2_2") (pintype "passive"))
    )
    (net (code "50") (name "unconnected-(P2-Pad2)") (class "Default")
      (node (ref "P2") (pin "2") (pinfunction "2_2") (pintype "passive+no_connect"))
    )
    (net (code "51") (name "unconnected-(P2-Pad3)") (class "Default")
      (node (ref "P2") (pin "3") (pinfunction "3_3") (pintype "passive+no_connect"))
    )
    (net (code "52") (name "unconnected-(P2-Pad4)") (class "Default")
      (node (ref "P2") (pin "4") (pinfunction "4_4") (pintype "passive+no_connect"))
    )
    (net (code "53") (name "unconnected-(U1-PA0-WKUP-Pad10)") (class "Default")
      (node (ref "U1") (pin "10") (pinfunction "PA0-WKUP_10") (pintype "bidirectional"))
    )
    (net (code "54") (name "unconnected-(U1-PA3-Pad13)") (class "Default")
      (node (ref "U1") (pin "13") (pinfunction "PA3_13") (pintype "bidirectional"))
    )
    (net (code "55") (name "unconnected-(U1-PA8-Pad29)") (class "Default")
      (node (ref "U1") (pin "29") (pinfunction "PA8_29") (pintype "bidirectional"))
    )
    (net (code "56") (name "unconnected-(U1-PA11-Pad32)") (class "Default")
      (node (ref "U1") (pin "32") (pinfunction "PA11_32") (pintype "bidirectional"))
    )
    (net (code "57") (name "unconnected-(U1-PA12-Pad33)") (class "Default")
      (node (ref "U1") (pin "33") (pinfunction "PA12_33") (pintype "bidirectional"))
    )
    (net (code "58") (name "unconnected-(U1-PA15{slash}JTDI-Pad38)") (class "Default")
      (node (ref "U1") (pin "38") (pinfunction "PA15/JTDI_38") (pintype "bidirectional"))
    )
    (net (code "59") (name "unconnected-(U1-PB1-Pad19)") (class "Default")
      (node (ref "U1") (pin "19") (pinfunction "PB1_19") (pintype "bidirectional"))
    )
    (net (code "60") (name "unconnected-(U1-PB3{slash}JTDO-Pad39)") (class "Default")
      (node (ref "U1") (pin "39") (pinfunction "PB3/JTDO_39") (pintype "bidirectional"))
    )
    (net (code "61") (name "unconnected-(U1-PB12-Pad25)") (class "Default")
      (node (ref "U1") (pin "25") (pinfunction "PB12_25") (pintype "bidirectional"))
    )
    (net (code "62") (name "unconnected-(U1-PB13-Pad26)") (class "Default")
      (node (ref "U1") (pin "26") (pinfunction "PB13_26") (pintype "bidirectional"))
    )
    (net (code "63") (name "unconnected-(U1-PB14-Pad27)") (class "Default")
      (node (ref "U1") (pin "27") (pinfunction "PB14_27") (pintype "bidirectional"))
    )
    (net (code "64") (name "unconnected-(U1-PB15-Pad28)") (class "Default")
      (node (ref "U1") (pin "28") (pinfunction "PB15_28") (pintype "bidirectional"))
    )
    (net (code "65") (name "unconnected-(U1-PC13-TAMPER-RTC-Pad2)") (class "Default")
      (node (ref "U1") (pin "2") (pinfunction "PC13-TAMPER-RTC_2") (pintype "bidirectional"))
    )
    (net (code "66") (name "unconnected-(U1-PC14-OSC32_IN-Pad3)") (class "Default")
      (node (ref "U1") (pin "3") (pinfunction "PC14-OSC32_IN_3") (pintype "bidirectional"))
    )
    (net (code "67") (name "unconnected-(U1-PC15-OSC32_OUT-Pad4)") (class "Default")
      (node (ref "U1") (pin "4") (pinfunction "PC15-OSC32_OUT_4") (pintype "bidirectional"))
    )
    (net (code "68") (name "unconnected-(U3-DRDY-Pad15)") (class "Default")
      (node (ref "U3") (pin "15") (pinfunction "DRDY_15") (pintype "passive+no_connect"))
    )
    (net (code "69") (name "unconnected-(U3-NC-Pad3)") (class "Default")
      (node (ref "U3") (pin "3") (pinfunction "NC_3") (pintype "passive+no_connect"))
    )
    (net (code "70") (name "unconnected-(U3-NC-Pad5)") (class "Default")
      (node (ref "U3") (pin "5") (pinfunction "NC_5") (pintype "passive+no_connect"))
    )
    (net (code "71") (name "unconnected-(U3-NC-Pad6)") (class "Default")
      (node (ref "U3") (pin "6") (pinfunction "NC_6") (pintype "passive+no_connect"))
    )
    (net (code "72") (name "unconnected-(U3-NC-Pad7)") (class "Default")
      (node (ref "U3") (pin "7") (pinfunction "NC_7") (pintype "passive+no_connect"))
    )
    (net (code "73") (name "unconnected-(U3-NC-Pad14)") (class "Default")
      (node (ref "U3") (pin "14") (pinfunction "NC_14") (pintype "passive+no_connect"))
    )
    (net (code "74") (name "unconnected-(U4-CLKOUT-Pad22)") (class "Default")
      (node (ref "U4") (pin "22") (pinfunction "CLKOUT_22") (pintype "passive+no_connect"))
    )
    (net (code "75") (name "unconnected-(U4-INT-Pad12)") (class "Default")
      (node (ref "U4") (pin "12") (pinfunction "INT_12") (pintype "passive+no_connect"))
    )
    (net (code "76") (name "unconnected-(U4-NC-Pad2)") (class "Default")
      (node (ref "U4") (pin "2") (pinfunction "NC_2") (pintype "passive+no_connect"))
    )
    (net (code "77") (name "unconnected-(U4-NC-Pad3)") (class "Default")
      (node (ref "U4") (pin "3") (pinfunction "NC_3") (pintype "passive+no_connect"))
    )
    (net (code "78") (name "unconnected-(U4-NC-Pad4)") (class "Default")
      (node (ref "U4") (pin "4") (pinfunction "NC_4") (pintype "passive+no_connect"))
    )
    (net (code "79") (name "unconnected-(U4-NC-Pad5)") (class "Default")
      (node (ref "U4") (pin "5") (pinfunction "NC_5") (pintype "passive+no_connect"))
    )
    (net (code "80") (name "unconnected-(U4-NC-Pad14)") (class "Default")
      (node (ref "U4") (pin "14") (pinfunction "NC_14") (pintype "passive+no_connect"))
    )
    (net (code "81") (name "unconnected-(U4-NC-Pad15)") (class "Default")
      (node (ref "U4") (pin "15") (pinfunction "NC_15") (pintype "passive+no_connect"))
    )
    (net (code "82") (name "unconnected-(U4-NC-Pad16)") (class "Default")
      (node (ref "U4") (pin "16") (pinfunction "NC_16") (pintype "passive+no_connect"))
    )
    (net (code "83") (name "unconnected-(U4-NC-Pad17)") (class "Default")
      (node (ref "U4") (pin "17") (pinfunction "NC_17") (pintype "passive+no_connect"))
    )
    (net (code "84") (name "unconnected-(U4-RESV-Pad19)") (class "Default")
      (node (ref "U4") (pin "19") (pinfunction "RESV_19") (pintype "passive+no_connect"))
    )
    (net (code "85") (name "unconnected-(U4-RESV-Pad21)") (class "Default")
      (node (ref "U4") (pin "21") (pinfunction "RESV_21") (pintype "passive+no_connect"))
    )
    (net (code "86") (name "unconnected-(U5-BYP-Pad4)") (class "Default")
      (node (ref "U5") (pin "4") (pinfunction "BYP_4") (pintype "passive"))
    )
  )
)
